# LAB04.net
KiCad netlist of a schematic drawn in Altium Designer
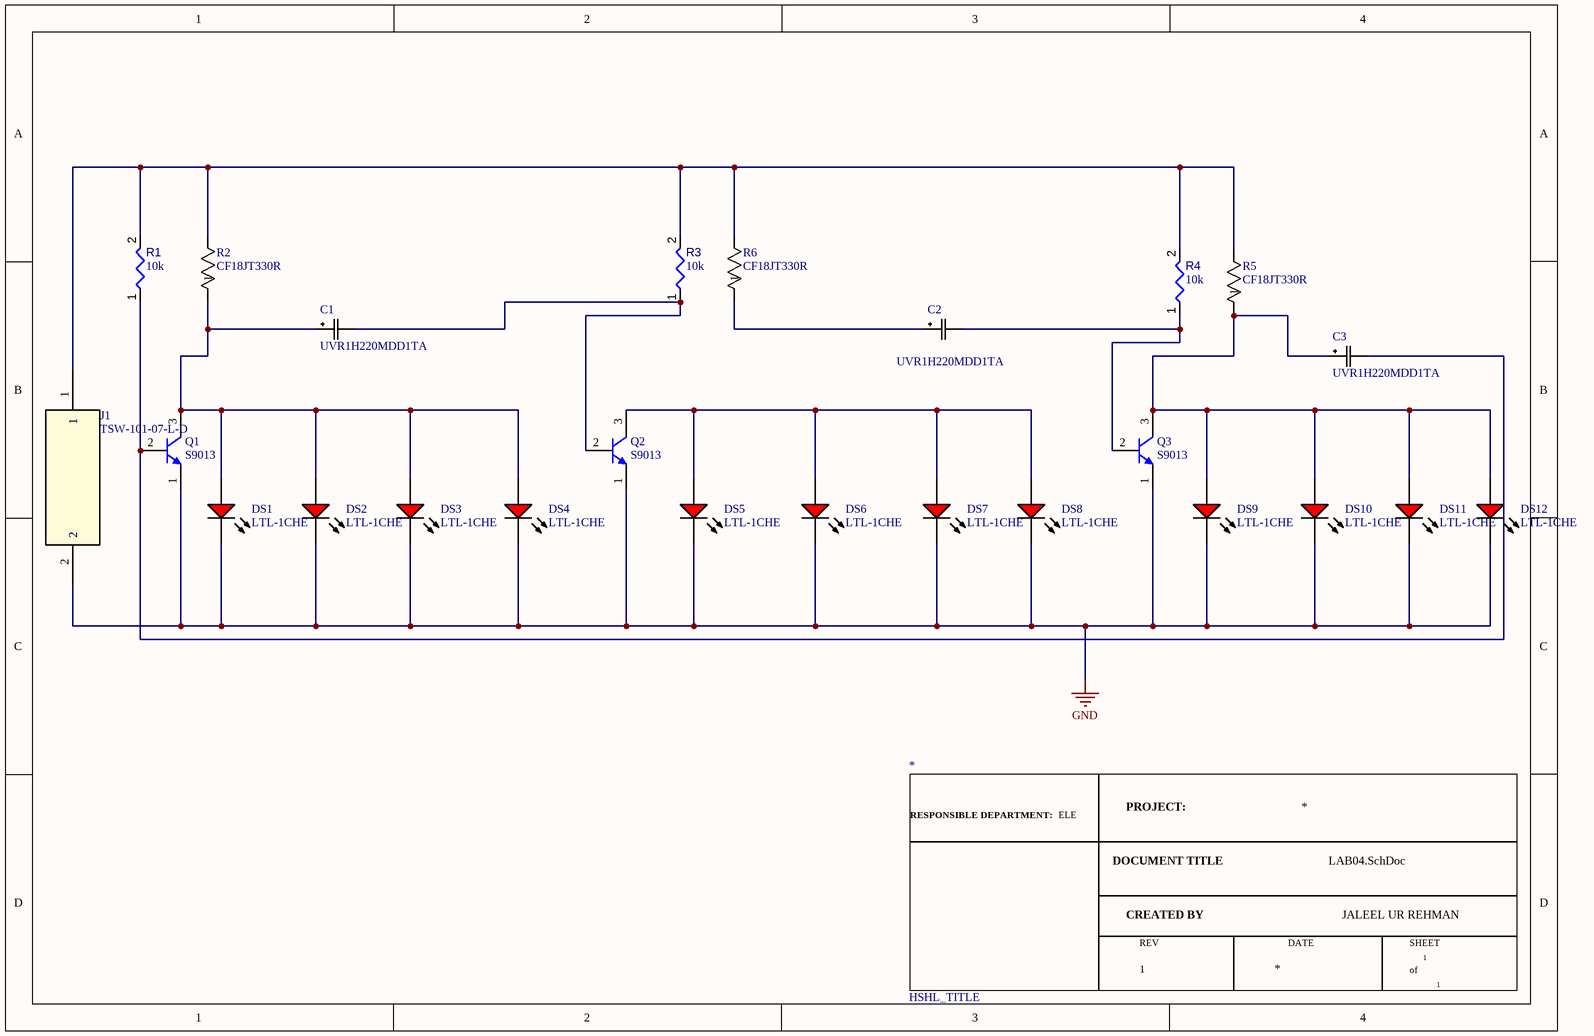
[diagram p0: LAB04.SchDoc]

(export (version "E")
  (design (tool "Eeschema 10.0.6"))
  (components
    (comp (ref "*") (value "HSHL_TITLE") (libsource (lib "Schlib1") (part "HSHL_TITLE")))
    (comp (ref "C1")
      (value "UVR1H220MDD1TA")
      (footprint "CAP_UEP_5X11_NCH")
      (description "No Description Available")
      (fields (field (name "COPYRIGHT") "Copyright (C) 2026 Ultra Librarian. All rights reserved."))
      (libsource (lib "UVR1H220MDD1TA") (part "UVR1H220MDD1TA"))
    )
    (comp (ref "C2")
      (value "UVR1H220MDD1TA")
      (footprint "CAP_UEP_5X11_NCH")
      (description "No Description Available")
      (fields (field (name "COPYRIGHT") "Copyright (C) 2026 Ultra Librarian. All rights reserved."))
      (libsource (lib "UVR1H220MDD1TA") (part "UVR1H220MDD1TA"))
    )
    (comp (ref "C3")
      (value "UVR1H220MDD1TA")
      (footprint "CAP_UEP_5X11_NCH")
      (description "No Description Available")
      (fields (field (name "COPYRIGHT") "Copyright (C) 2026 Ultra Librarian. All rights reserved."))
      (libsource (lib "UVR1H220MDD1TA") (part "UVR1H220MDD1TA"))
    )
    (comp (ref "DS1")
      (value "LTL-1CHE")
      (footprint "INDPR60-254-520X380X650")
      (description "LED Uni-Color Red, 100 mW, 30 mA, -55 to 100 degC, 2-Pin THD, RoHS, Bulk")
      (fields (field (name "MANUFACTURER") "Lite-On"))
      (libsource (lib "jaleel ur rehman") (part "LED-RED-AK-2"))
    )
    (comp (ref "DS2")
      (value "LTL-1CHE")
      (footprint "INDPR60-254-520X380X650")
      (description "LED Uni-Color Red, 100 mW, 30 mA, -55 to 100 degC, 2-Pin THD, RoHS, Bulk")
      (fields (field (name "MANUFACTURER") "Lite-On"))
      (libsource (lib "jaleel ur rehman") (part "LED-RED-AK-2"))
    )
    (comp (ref "DS3")
      (value "LTL-1CHE")
      (footprint "INDPR60-254-520X380X650")
      (description "LED Uni-Color Red, 100 mW, 30 mA, -55 to 100 degC, 2-Pin THD, RoHS, Bulk")
      (fields (field (name "MANUFACTURER") "Lite-On"))
      (libsource (lib "jaleel ur rehman") (part "LED-RED-AK-2"))
    )
    (comp (ref "DS4")
      (value "LTL-1CHE")
      (footprint "INDPR60-254-520X380X650")
      (description "LED Uni-Color Red, 100 mW, 30 mA, -55 to 100 degC, 2-Pin THD, RoHS, Bulk")
      (fields (field (name "MANUFACTURER") "Lite-On"))
      (libsource (lib "jaleel ur rehman") (part "LED-RED-AK-2"))
    )
    (comp (ref "DS5")
      (value "LTL-1CHE")
      (footprint "INDPR60-254-520X380X650")
      (description "LED Uni-Color Red, 100 mW, 30 mA, -55 to 100 degC, 2-Pin THD, RoHS, Bulk")
      (fields (field (name "MANUFACTURER") "Lite-On"))
      (libsource (lib "jaleel ur rehman") (part "LED-RED-AK-2"))
    )
    (comp (ref "DS6")
      (value "LTL-1CHE")
      (footprint "INDPR60-254-520X380X650")
      (description "LED Uni-Color Red, 100 mW, 30 mA, -55 to 100 degC, 2-Pin THD, RoHS, Bulk")
      (fields (field (name "MANUFACTURER") "Lite-On"))
      (libsource (lib "jaleel ur rehman") (part "LED-RED-AK-2"))
    )
    (comp (ref "DS7")
      (value "LTL-1CHE")
      (footprint "INDPR60-254-520X380X650")
      (description "LED Uni-Color Red, 100 mW, 30 mA, -55 to 100 degC, 2-Pin THD, RoHS, Bulk")
      (fields (field (name "MANUFACTURER") "Lite-On"))
      (libsource (lib "jaleel ur rehman") (part "LED-RED-AK-2"))
    )
    (comp (ref "DS8")
      (value "LTL-1CHE")
      (footprint "INDPR60-254-520X380X650")
      (description "LED Uni-Color Red, 100 mW, 30 mA, -55 to 100 degC, 2-Pin THD, RoHS, Bulk")
      (fields (field (name "MANUFACTURER") "Lite-On"))
      (libsource (lib "jaleel ur rehman") (part "LED-RED-AK-2"))
    )
    (comp (ref "DS9")
      (value "LTL-1CHE")
      (footprint "INDPR60-254-520X380X650")
      (description "LED Uni-Color Red, 100 mW, 30 mA, -55 to 100 degC, 2-Pin THD, RoHS, Bulk")
      (fields (field (name "MANUFACTURER") "Lite-On"))
      (libsource (lib "jaleel ur rehman") (part "LED-RED-AK-2"))
    )
    (comp (ref "DS10")
      (value "LTL-1CHE")
      (footprint "INDPR60-254-520X380X650")
      (description "LED Uni-Color Red, 100 mW, 30 mA, -55 to 100 degC, 2-Pin THD, RoHS, Bulk")
      (fields (field (name "MANUFACTURER") "Lite-On"))
      (libsource (lib "jaleel ur rehman") (part "LED-RED-AK-2"))
    )
    (comp (ref "DS11")
      (value "LTL-1CHE")
      (footprint "INDPR60-254-520X380X650")
      (description "LED Uni-Color Red, 100 mW, 30 mA, -55 to 100 degC, 2-Pin THD, RoHS, Bulk")
      (fields (field (name "MANUFACTURER") "Lite-On"))
      (libsource (lib "jaleel ur rehman") (part "LED-RED-AK-2"))
    )
    (comp (ref "DS12")
      (value "LTL-1CHE")
      (footprint "INDPR60-254-520X380X650")
      (description "LED Uni-Color Red, 100 mW, 30 mA, -55 to 100 degC, 2-Pin THD, RoHS, Bulk")
      (fields (field (name "MANUFACTURER") "Lite-On"))
      (libsource (lib "jaleel ur rehman") (part "LED-RED-AK-2"))
    )
    (comp (ref "J1")
      (value "TSW-101-07-L-D")
      (footprint "TSW-101-07-G-D_SAI")
      (description "Description")
      (fields (field (name "COPYRIGHT") "Copyright (C) 2026 Ultra Librarian. All rights reserved."))
      (libsource (lib "TSW-101-07-L-D") (part "TSW-101-07-L-D"))
    )
    (comp (ref "Q1")
      (value "S9013")
      (footprint "JSCJ-TO-92-3_V")
      (description "Transistor, NPN, 0.1 uA, 150 MHz, 3-Pin TO-92")
      (fields (field (name "MANUFACTURER") "Jiangsu Changjiang Electronics Technology"))
      (libsource (lib "jaleel ur rehman") (part "BJT-NPN-EBC-3"))
    )
    (comp (ref "Q2")
      (value "S9013")
      (footprint "JSCJ-TO-92-3_V")
      (description "Transistor, NPN, 0.1 uA, 150 MHz, 3-Pin TO-92")
      (fields (field (name "MANUFACTURER") "Jiangsu Changjiang Electronics Technology"))
      (libsource (lib "jaleel ur rehman") (part "BJT-NPN-EBC-3"))
    )
    (comp (ref "Q3")
      (value "S9013")
      (footprint "JSCJ-TO-92-3_V")
      (description "Transistor, NPN, 0.1 uA, 150 MHz, 3-Pin TO-92")
      (fields (field (name "MANUFACTURER") "Jiangsu Changjiang Electronics Technology"))
      (libsource (lib "jaleel ur rehman") (part "BJT-NPN-EBC-3"))
    )
    (comp (ref "R1")
      (value "10k")
      (footprint "RESA60-630X240")
      (description "Axial Resistor, 10 KOhm, +/- 1%, 0.25 W, -55 to 155 degC, 2-Pin THD, RoHS, Bulk")
      (fields (field (name "TOLERANCE") "1%") (field (name "POWER") "250mW"))
      (libsource (lib "jaleel ur rehman") (part "RES-2"))
    )
    (comp (ref "R2")
      (value "CF18JT330R")
      (footprint "STA_CF18_STP")
      (description "Description")
      (fields (field (name "COPYRIGHT") "Copyright (C) 2025 Ultra Librarian. All rights reserved."))
      (libsource (lib "CF18JT330R") (part "CF18JT330R"))
    )
    (comp (ref "R3")
      (value "10k")
      (footprint "RESA60-630X240")
      (description "Axial Resistor, 10 KOhm, +/- 1%, 0.25 W, -55 to 155 degC, 2-Pin THD, RoHS, Bulk")
      (fields (field (name "TOLERANCE") "1%") (field (name "POWER") "250mW"))
      (libsource (lib "jaleel ur rehman") (part "RES-2"))
    )
    (comp (ref "R4")
      (value "10k")
      (footprint "RESA60-630X240")
      (description "Axial Resistor, 10 KOhm, +/- 1%, 0.25 W, -55 to 155 degC, 2-Pin THD, RoHS, Bulk")
      (fields (field (name "TOLERANCE") "1%") (field (name "POWER") "250mW"))
      (libsource (lib "jaleel ur rehman") (part "RES-2"))
    )
    (comp (ref "R5")
      (value "CF18JT330R")
      (footprint "STA_CF18_STP")
      (description "Description")
      (fields (field (name "COPYRIGHT") "Copyright (C) 2025 Ultra Librarian. All rights reserved."))
      (libsource (lib "CF18JT330R") (part "CF18JT330R"))
    )
    (comp (ref "R6")
      (value "CF18JT330R")
      (footprint "STA_CF18_STP")
      (description "Description")
      (fields (field (name "COPYRIGHT") "Copyright (C) 2025 Ultra Librarian. All rights reserved."))
      (libsource (lib "CF18JT330R") (part "CF18JT330R"))
    )
  )
  (nets
    (net (code "1") (name "GND") (class "Default")
      (node (ref "DS1") (pin "2") (pinfunction "K_2") (pintype "passive"))
      (node (ref "DS10") (pin "2") (pinfunction "K_2") (pintype "passive"))
      (node (ref "DS11") (pin "2") (pinfunction "K_2") (pintype "passive"))
      (node (ref "DS12") (pin "2") (pinfunction "K_2") (pintype "passive"))
      (node (ref "DS2") (pin "2") (pinfunction "K_2") (pintype "passive"))
      (node (ref "DS3") (pin "2") (pinfunction "K_2") (pintype "passive"))
      (node (ref "DS4") (pin "2") (pinfunction "K_2") (pintype "passive"))
      (node (ref "DS5") (pin "2") (pinfunction "K_2") (pintype "passive"))
      (node (ref "DS6") (pin "2") (pinfunction "K_2") (pintype "passive"))
      (node (ref "DS7") (pin "2") (pinfunction "K_2") (pintype "passive"))
      (node (ref "DS8") (pin "2") (pinfunction "K_2") (pintype "passive"))
      (node (ref "DS9") (pin "2") (pinfunction "K_2") (pintype "passive"))
      (node (ref "J1") (pin "2") (pinfunction "2_2") (pintype "passive"))
      (node (ref "Q1") (pin "1") (pinfunction "E_1") (pintype "passive"))
      (node (ref "Q2") (pin "1") (pinfunction "E_1") (pintype "passive"))
      (node (ref "Q3") (pin "1") (pinfunction "E_1") (pintype "passive"))
    )
    (net (code "2") (name "Net-(C2-Pad1)") (class "Default")
      (node (ref "C2") (pin "1") (pinfunction "1_1") (pintype "passive"))
      (node (ref "R6") (pin "1") (pinfunction "1_1") (pintype "passive"))
    )
    (net (code "3") (name "Net-(DS1-A)") (class "Default")
      (node (ref "C1") (pin "1") (pinfunction "1_1") (pintype "passive"))
      (node (ref "DS1") (pin "1") (pinfunction "A_1") (pintype "passive"))
      (node (ref "DS2") (pin "1") (pinfunction "A_1") (pintype "passive"))
      (node (ref "DS3") (pin "1") (pinfunction "A_1") (pintype "passive"))
      (node (ref "DS4") (pin "1") (pinfunction "A_1") (pintype "passive"))
      (node (ref "Q1") (pin "3") (pinfunction "C_3") (pintype "passive"))
      (node (ref "R2") (pin "1") (pinfunction "1_1") (pintype "passive"))
    )
    (net (code "4") (name "Net-(DS5-A)") (class "Default")
      (node (ref "DS5") (pin "1") (pinfunction "A_1") (pintype "passive"))
      (node (ref "DS6") (pin "1") (pinfunction "A_1") (pintype "passive"))
      (node (ref "DS7") (pin "1") (pinfunction "A_1") (pintype "passive"))
      (node (ref "DS8") (pin "1") (pinfunction "A_1") (pintype "passive"))
      (node (ref "Q2") (pin "3") (pinfunction "C_3") (pintype "passive"))
    )
    (net (code "5") (name "Net-(DS10-A)") (class "Default")
      (node (ref "C3") (pin "1") (pinfunction "1_1") (pintype "passive"))
      (node (ref "DS10") (pin "1") (pinfunction "A_1") (pintype "passive"))
      (node (ref "DS11") (pin "1") (pinfunction "A_1") (pintype "passive"))
      (node (ref "DS12") (pin "1") (pinfunction "A_1") (pintype "passive"))
      (node (ref "DS9") (pin "1") (pinfunction "A_1") (pintype "passive"))
      (node (ref "Q3") (pin "3") (pinfunction "C_3") (pintype "passive"))
      (node (ref "R5") (pin "1") (pinfunction "1_1") (pintype "passive"))
    )
    (net (code "6") (name "Net-(J1-Pad1)") (class "Default")
      (node (ref "J1") (pin "1") (pinfunction "1_1") (pintype "passive"))
      (node (ref "R1") (pin "2") (pinfunction "2_2") (pintype "passive"))
      (node (ref "R2") (pin "2") (pinfunction "2_2") (pintype "passive"))
      (node (ref "R3") (pin "2") (pinfunction "2_2") (pintype "passive"))
      (node (ref "R4") (pin "2") (pinfunction "2_2") (pintype "passive"))
      (node (ref "R5") (pin "2") (pinfunction "2_2") (pintype "passive"))
      (node (ref "R6") (pin "2") (pinfunction "2_2") (pintype "passive"))
    )
    (net (code "7") (name "Net-(Q1-B)") (class "Default")
      (node (ref "C3") (pin "2") (pinfunction "2_2") (pintype "passive"))
      (node (ref "Q1") (pin "2") (pinfunction "B_2") (pintype "passive"))
      (node (ref "R1") (pin "1") (pinfunction "1_1") (pintype "passive"))
    )
    (net (code "8") (name "Net-(Q2-B)") (class "Default")
      (node (ref "C1") (pin "2") (pinfunction "2_2") (pintype "passive"))
      (node (ref "Q2") (pin "2") (pinfunction "B_2") (pintype "passive"))
      (node (ref "R3") (pin "1") (pinfunction "1_1") (pintype "passive"))
    )
    (net (code "9") (name "Net-(Q3-B)") (class "Default")
      (node (ref "C2") (pin "2") (pinfunction "2_2") (pintype "passive"))
      (node (ref "Q3") (pin "2") (pinfunction "B_2") (pintype "passive"))
      (node (ref "R4") (pin "1") (pinfunction "1_1") (pintype "passive"))
    )
  )
)
